# BLE112_Module.net
KiCad netlist of a schematic drawn in Altium Designer
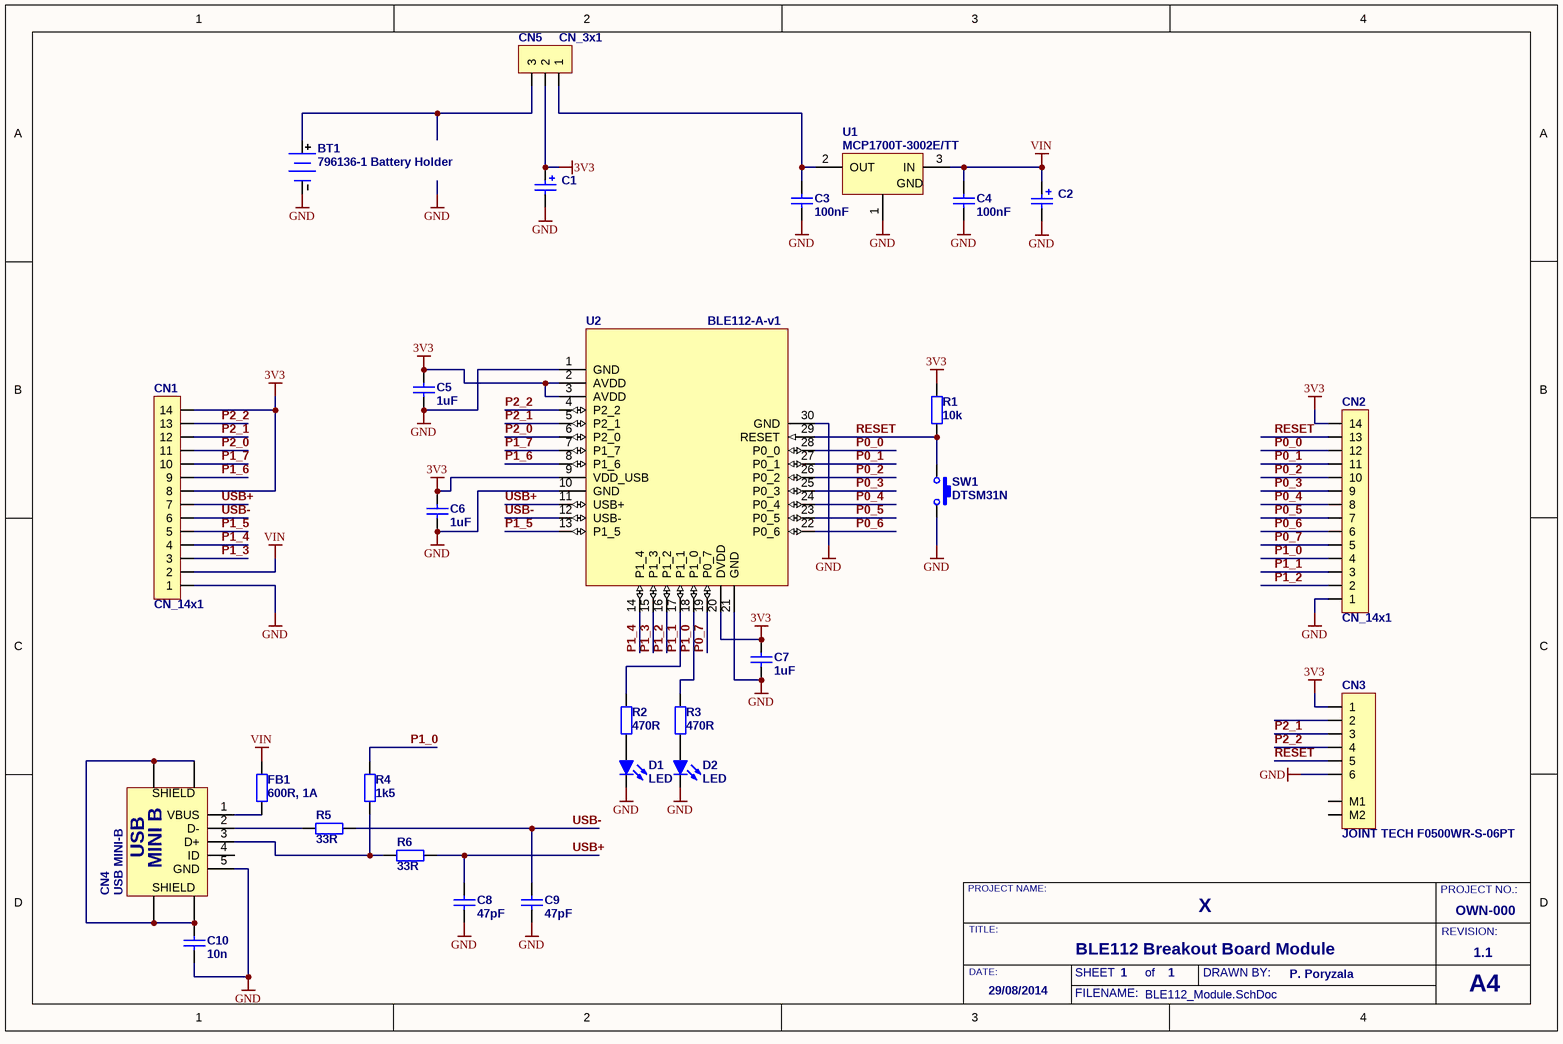
[diagram p0: BLE112_Module.SchDoc]

(export (version "E")
  (design (tool "Eeschema 10.0.6"))
  (components
    (comp (ref "BT1")
      (value "796136-1 Battery Holder")
      (footprint "796136-1")
      (description "Tyco Connectivity 796136-1 CR2032 Battery Holder")
      (fields (field (name "PUBLISHER") "Altium Limited"))
      (libsource (lib "baterries_and_accus") (part "796136-1"))
    )
    (comp (ref "C1")
      (value "~")
      (footprint "SMDB")
      (description "Polarized Tantalum Capacitor")
      (libsource (lib "capacitors") (part "Cap Pol Tant"))
    )
    (comp (ref "C2")
      (value "~")
      (footprint "SMDB")
      (description "Polarized Tantalum Capacitor")
      (libsource (lib "capacitors") (part "Cap Pol Tant"))
    )
    (comp (ref "C3")
      (value "100nF")
      (footprint "C0603")
      (description "Capacitor")
      (libsource (lib "capacitors") (part "Cap"))
    )
    (comp (ref "C4")
      (value "100nF")
      (footprint "C0603")
      (description "Capacitor")
      (libsource (lib "capacitors") (part "Cap"))
    )
    (comp (ref "C5")
      (value "1uF")
      (footprint "C0603")
      (description "Capacitor")
      (libsource (lib "capacitors") (part "Cap"))
    )
    (comp (ref "C6")
      (value "1uF")
      (footprint "C0603")
      (description "Capacitor")
      (libsource (lib "capacitors") (part "Cap"))
    )
    (comp (ref "C7")
      (value "1uF")
      (footprint "C0603")
      (description "Capacitor")
      (libsource (lib "capacitors") (part "Cap"))
    )
    (comp (ref "C8")
      (value "47pF")
      (footprint "C0603")
      (description "Capacitor")
      (libsource (lib "capacitors") (part "Cap"))
    )
    (comp (ref "C9")
      (value "47pF")
      (footprint "C0603")
      (description "Capacitor")
      (libsource (lib "capacitors") (part "Cap"))
    )
    (comp (ref "C10")
      (value "10n")
      (footprint "C0603")
      (description "Capacitor")
      (libsource (lib "capacitors") (part "Cap"))
    )
    (comp (ref "CN1") (value "CN_14x1") (footprint "GP_14x1") (libsource (lib "") (part "CN_14x1_1")))
    (comp (ref "CN2")
      (value "CN_14x1")
      (footprint "GP_14x1")
      (libsource (lib "goldpin_male") (part "CN_14x1"))
    )
    (comp (ref "CN3")
      (value "JOINT TECH F0500WR-S-06PT")
      (footprint "F0500WR-S-06PT")
      (description "0.50mm Pitch FFC/FPC Connector, SMT, Right Angle, ZIF, Top Contact Style Receptacle, 6 Circuits")
      (libsource (lib "ffc_fpc") (part "JOINT TECH F0500WR-S-06PT"))
    )
    (comp (ref "CN4")
      (value "USB MINI-B")
      (footprint "USB-MINI-B SMD")
      (description "USB Mini-B Receptacle")
      (libsource (lib "usb") (part "USB MINI-B"))
    )
    (comp (ref "CN5") (value "CN_3x1") (footprint "GP_3x1") (libsource (lib "goldpin_male") (part "CN_3x1")))
    (comp (ref "D1")
      (value "LED")
      (footprint "LED0603B")
      (description "Typical RED, GREEN, YELLOW, AMBER GaAs LED")
      (libsource (lib "leds") (part "LED"))
    )
    (comp (ref "D2")
      (value "LED")
      (footprint "LED0603R")
      (description "Typical RED, GREEN, YELLOW, AMBER GaAs LED")
      (libsource (lib "leds") (part "LED"))
    )
    (comp (ref "FB1")
      (value "600R, 1A")
      (footprint "FB0603")
      (description "Ferrite Bead; Imp.@ 100MHz:600R; Mounting: SMD; 1A; Case: 0603")
      (libsource (lib "emi_emc_ferrites") (part "LCBA-601"))
    )
    (comp (ref "R1")
      (value "10k")
      (footprint "R0603")
      (description "Resistor")
      (libsource (lib "resistors") (part "Res"))
    )
    (comp (ref "R2")
      (value "470R")
      (footprint "R0603")
      (description "Resistor")
      (libsource (lib "resistors") (part "Res"))
    )
    (comp (ref "R3")
      (value "470R")
      (footprint "R0603")
      (description "Resistor")
      (libsource (lib "resistors") (part "Res"))
    )
    (comp (ref "R4")
      (value "1k5")
      (footprint "R0603")
      (description "Resistor")
      (libsource (lib "") (part "Res_1"))
    )
    (comp (ref "R5")
      (value "33R")
      (footprint "R0603")
      (description "Resistor")
      (libsource (lib "") (part "Res_2"))
    )
    (comp (ref "R6")
      (value "33R")
      (footprint "R0603")
      (description "Resistor")
      (libsource (lib "") (part "Res_2"))
    )
    (comp (ref "SW1")
      (value "DTSM31N")
      (footprint "DTSM-3")
      (description "DIPTRONICS 6x3,5mm SMD Tactile SPST-NO Switch")
      (libsource (lib "microswitches") (part "DTSM31N"))
    )
    (comp (ref "U1")
      (value "MCP1700T-3002E/TT")
      (footprint "SOT-23")
      (description "250mA, Low Voltage, Low Quiescent Current (1.6uA) LDO Voltage Regulator")
      (fields (field (name "PUBLISHER") "Altium Limited"))
      (libsource (lib "voltage_regulators") (part "MCP1700T-3002E/TT"))
    )
    (comp (ref "U2")
      (value "BLE112-A-v1")
      (footprint "BLE112-x")
      (description "Bluetooth ®  low energy single mode module")
      (libsource (lib "rf_modules") (part "BLE112-A-v1"))
    )
  )
  (nets
    (net (code "1") (name "/P0_0") (class "Default")
      (node (ref "CN2") (pin "12") (pinfunction "12_12") (pintype "passive"))
      (node (ref "U2") (pin "28") (pinfunction "P0_0_28") (pintype "bidirectional"))
    )
    (net (code "2") (name "/P0_1") (class "Default")
      (node (ref "CN2") (pin "11") (pinfunction "11_11") (pintype "passive"))
      (node (ref "U2") (pin "27") (pinfunction "P0_1_27") (pintype "bidirectional"))
    )
    (net (code "3") (name "/P0_2") (class "Default")
      (node (ref "CN2") (pin "10") (pinfunction "10_10") (pintype "passive"))
      (node (ref "U2") (pin "26") (pinfunction "P0_2_26") (pintype "bidirectional"))
    )
    (net (code "4") (name "/P0_3") (class "Default")
      (node (ref "CN2") (pin "9") (pinfunction "9_9") (pintype "passive"))
      (node (ref "U2") (pin "25") (pinfunction "P0_3_25") (pintype "bidirectional"))
    )
    (net (code "5") (name "/P0_4") (class "Default")
      (node (ref "CN2") (pin "8") (pinfunction "8_8") (pintype "passive"))
      (node (ref "U2") (pin "24") (pinfunction "P0_4_24") (pintype "bidirectional"))
    )
    (net (code "6") (name "/P0_5") (class "Default")
      (node (ref "CN2") (pin "7") (pinfunction "7_7") (pintype "passive"))
      (node (ref "U2") (pin "23") (pinfunction "P0_5_23") (pintype "bidirectional"))
    )
    (net (code "7") (name "/P0_6") (class "Default")
      (node (ref "CN2") (pin "6") (pinfunction "6_6") (pintype "passive"))
      (node (ref "U2") (pin "22") (pinfunction "P0_6_22") (pintype "bidirectional"))
    )
    (net (code "8") (name "/P0_7") (class "Default")
      (node (ref "CN2") (pin "5") (pinfunction "5_5") (pintype "passive"))
      (node (ref "U2") (pin "19") (pinfunction "P0_7_19") (pintype "bidirectional"))
    )
    (net (code "9") (name "/P1_0") (class "Default")
      (node (ref "CN2") (pin "4") (pinfunction "4_4") (pintype "passive"))
      (node (ref "R3") (pin "2") (pinfunction "2_2") (pintype "passive"))
      (node (ref "R4") (pin "1") (pinfunction "1_1") (pintype "passive"))
      (node (ref "U2") (pin "18") (pinfunction "P1_0_18") (pintype "bidirectional"))
    )
    (net (code "10") (name "/P1_1") (class "Default")
      (node (ref "CN2") (pin "3") (pinfunction "3_3") (pintype "passive"))
      (node (ref "R2") (pin "2") (pinfunction "2_2") (pintype "passive"))
      (node (ref "U2") (pin "17") (pinfunction "P1_1_17") (pintype "bidirectional"))
    )
    (net (code "11") (name "/P1_2") (class "Default")
      (node (ref "CN2") (pin "2") (pinfunction "2_2") (pintype "passive"))
      (node (ref "U2") (pin "16") (pinfunction "P1_2_16") (pintype "bidirectional"))
    )
    (net (code "12") (name "/P1_3") (class "Default")
      (node (ref "CN1") (pin "3") (pinfunction "3_3") (pintype "passive"))
      (node (ref "U2") (pin "15") (pinfunction "P1_3_15") (pintype "bidirectional"))
    )
    (net (code "13") (name "/P1_4") (class "Default")
      (node (ref "CN1") (pin "4") (pinfunction "4_4") (pintype "passive"))
      (node (ref "U2") (pin "14") (pinfunction "P1_4_14") (pintype "bidirectional"))
    )
    (net (code "14") (name "/P1_5") (class "Default")
      (node (ref "CN1") (pin "5") (pinfunction "5_5") (pintype "passive"))
      (node (ref "U2") (pin "13") (pinfunction "P1_5_13") (pintype "bidirectional"))
    )
    (net (code "15") (name "/P1_6") (class "Default")
      (node (ref "CN1") (pin "9") (pinfunction "9_9") (pintype "passive"))
      (node (ref "U2") (pin "8") (pinfunction "P1_6_8") (pintype "bidirectional"))
    )
    (net (code "16") (name "/P1_7") (class "Default")
      (node (ref "CN1") (pin "10") (pinfunction "10_10") (pintype "passive"))
      (node (ref "U2") (pin "7") (pinfunction "P1_7_7") (pintype "bidirectional"))
    )
    (net (code "17") (name "/P2_0") (class "Default")
      (node (ref "CN1") (pin "11") (pinfunction "11_11") (pintype "passive"))
      (node (ref "U2") (pin "6") (pinfunction "P2_0_6") (pintype "bidirectional"))
    )
    (net (code "18") (name "/P2_1") (class "Default")
      (node (ref "CN1") (pin "12") (pinfunction "12_12") (pintype "passive"))
      (node (ref "CN3") (pin "3") (pinfunction "3_3") (pintype "passive"))
      (node (ref "U2") (pin "5") (pinfunction "P2_1_5") (pintype "bidirectional"))
    )
    (net (code "19") (name "/P2_2") (class "Default")
      (node (ref "CN1") (pin "13") (pinfunction "13_13") (pintype "passive"))
      (node (ref "CN3") (pin "4") (pinfunction "4_4") (pintype "passive"))
      (node (ref "U2") (pin "4") (pinfunction "P2_2_4") (pintype "bidirectional"))
    )
    (net (code "20") (name "/RESET") (class "Default")
      (node (ref "CN2") (pin "13") (pinfunction "13_13") (pintype "passive"))
      (node (ref "CN3") (pin "5") (pinfunction "5_5") (pintype "passive"))
      (node (ref "R1") (pin "1") (pinfunction "1_1") (pintype "passive"))
      (node (ref "SW1") (pin "1") (pinfunction "1_1") (pintype "passive"))
      (node (ref "U2") (pin "29") (pinfunction "RESET_29") (pintype "input"))
    )
    (net (code "21") (name "/USB+") (class "Default")
      (node (ref "C8") (pin "2") (pinfunction "2_2") (pintype "passive"))
      (node (ref "CN1") (pin "7") (pinfunction "7_7") (pintype "passive"))
      (node (ref "R6") (pin "1") (pinfunction "1_1") (pintype "passive"))
      (node (ref "U2") (pin "11") (pinfunction "USB+_11") (pintype "bidirectional"))
    )
    (net (code "22") (name "/USB-") (class "Default")
      (node (ref "C9") (pin "2") (pinfunction "2_2") (pintype "passive"))
      (node (ref "CN1") (pin "6") (pinfunction "6_6") (pintype "passive"))
      (node (ref "R5") (pin "1") (pinfunction "1_1") (pintype "passive"))
      (node (ref "U2") (pin "12") (pinfunction "USB-_12") (pintype "bidirectional"))
    )
    (net (code "23") (name "3V3") (class "Default")
      (node (ref "C1") (pin "1") (pinfunction "1_1") (pintype "passive"))
      (node (ref "C5") (pin "2") (pinfunction "2_2") (pintype "passive"))
      (node (ref "C6") (pin "2") (pinfunction "2_2") (pintype "passive"))
      (node (ref "C7") (pin "2") (pinfunction "2_2") (pintype "passive"))
      (node (ref "CN1") (pin "14") (pinfunction "14_14") (pintype "passive"))
      (node (ref "CN1") (pin "8") (pinfunction "8_8") (pintype "passive"))
      (node (ref "CN2") (pin "14") (pinfunction "14_14") (pintype "passive"))
      (node (ref "CN3") (pin "1") (pinfunction "1_1") (pintype "passive"))
      (node (ref "CN5") (pin "2") (pinfunction "2_2") (pintype "passive"))
      (node (ref "R1") (pin "2") (pinfunction "2_2") (pintype "passive"))
      (node (ref "U2") (pin "2") (pinfunction "AVDD_2") (pintype "power_in"))
      (node (ref "U2") (pin "20") (pinfunction "DVDD_20") (pintype "power_in"))
      (node (ref "U2") (pin "3") (pinfunction "AVDD_3") (pintype "power_in"))
      (node (ref "U2") (pin "9") (pinfunction "VDD_USB_9") (pintype "power_in"))
    )
    (net (code "24") (name "GND") (class "Default")
      (node (ref "BT1") (pin "2") (pinfunction "-_2") (pintype "passive"))
      (node (ref "C1") (pin "2") (pinfunction "2_2") (pintype "passive"))
      (node (ref "C10") (pin "1") (pinfunction "1_1") (pintype "passive"))
      (node (ref "C2") (pin "2") (pinfunction "2_2") (pintype "passive"))
      (node (ref "C3") (pin "1") (pinfunction "1_1") (pintype "passive"))
      (node (ref "C4") (pin "1") (pinfunction "1_1") (pintype "passive"))
      (node (ref "C5") (pin "1") (pinfunction "1_1") (pintype "passive"))
      (node (ref "C6") (pin "1") (pinfunction "1_1") (pintype "passive"))
      (node (ref "C7") (pin "1") (pinfunction "1_1") (pintype "passive"))
      (node (ref "C8") (pin "1") (pinfunction "1_1") (pintype "passive"))
      (node (ref "C9") (pin "1") (pinfunction "1_1") (pintype "passive"))
      (node (ref "CN1") (pin "1") (pinfunction "1_1") (pintype "passive"))
      (node (ref "CN2") (pin "1") (pinfunction "1_1") (pintype "passive"))
      (node (ref "CN3") (pin "6") (pinfunction "6_6") (pintype "passive"))
      (node (ref "CN4") (pin "5") (pinfunction "GND_5") (pintype "passive"))
      (node (ref "D1") (pin "2") (pinfunction "K_2") (pintype "passive"))
      (node (ref "D2") (pin "2") (pinfunction "K_2") (pintype "passive"))
      (node (ref "SW1") (pin "2") (pinfunction "2_2") (pintype "passive"))
      (node (ref "U1") (pin "1") (pinfunction "GND_1") (pintype "power_in"))
      (node (ref "U2") (pin "1") (pinfunction "GND_1") (pintype "power_in"))
      (node (ref "U2") (pin "10") (pinfunction "GND_10") (pintype "power_in"))
      (node (ref "U2") (pin "21") (pinfunction "GND_21") (pintype "power_in"))
      (node (ref "U2") (pin "30") (pinfunction "GND_30") (pintype "power_in"))
    )
    (net (code "25") (name "Net-(BT1-+)") (class "Default")
      (node (ref "BT1") (pin "1") (pinfunction "+_1") (pintype "passive"))
      (node (ref "CN5") (pin "3") (pinfunction "3_3") (pintype "passive"))
    )
    (net (code "26") (name "Net-(C10-Pad2)") (class "Default")
      (node (ref "C10") (pin "2") (pinfunction "2_2") (pintype "passive"))
      (node (ref "CN4") (pin "6") (pinfunction "SHIELD_6") (pintype "passive"))
      (node (ref "CN4") (pin "7") (pinfunction "SHIELD_7") (pintype "passive"))
      (node (ref "CN4") (pin "8") (pinfunction "SHIELD_8") (pintype "passive"))
      (node (ref "CN4") (pin "9") (pinfunction "SHIELD_9") (pintype "passive"))
    )
    (net (code "27") (name "Net-(CN4-D+)") (class "Default")
      (node (ref "CN4") (pin "3") (pinfunction "D+_3") (pintype "passive"))
      (node (ref "R4") (pin "2") (pinfunction "2_2") (pintype "passive"))
      (node (ref "R6") (pin "2") (pinfunction "2_2") (pintype "passive"))
    )
    (net (code "28") (name "Net-(CN4-D-)") (class "Default")
      (node (ref "CN4") (pin "2") (pinfunction "D-_2") (pintype "passive"))
      (node (ref "R5") (pin "2") (pinfunction "2_2") (pintype "passive"))
    )
    (net (code "29") (name "Net-(CN4-VBUS)") (class "Default")
      (node (ref "CN4") (pin "1") (pinfunction "VBUS_1") (pintype "passive"))
      (node (ref "FB1") (pin "1") (pinfunction "1_1") (pintype "passive"))
    )
    (net (code "30") (name "Net-(D1-A)") (class "Default")
      (node (ref "D1") (pin "1") (pinfunction "A_1") (pintype "passive"))
      (node (ref "R2") (pin "1") (pinfunction "1_1") (pintype "passive"))
    )
    (net (code "31") (name "Net-(D2-A)") (class "Default")
      (node (ref "D2") (pin "1") (pinfunction "A_1") (pintype "passive"))
      (node (ref "R3") (pin "1") (pinfunction "1_1") (pintype "passive"))
    )
    (net (code "32") (name "Net-(U1-OUT)") (class "Default")
      (node (ref "C3") (pin "2") (pinfunction "2_2") (pintype "passive"))
      (node (ref "CN5") (pin "1") (pinfunction "1_1") (pintype "passive"))
      (node (ref "U1") (pin "2") (pinfunction "OUT_2") (pintype "power_in"))
    )
    (net (code "33") (name "VIN") (class "Default")
      (node (ref "C2") (pin "1") (pinfunction "1_1") (pintype "passive"))
      (node (ref "C4") (pin "2") (pinfunction "2_2") (pintype "passive"))
      (node (ref "CN1") (pin "2") (pinfunction "2_2") (pintype "passive"))
      (node (ref "FB1") (pin "2") (pinfunction "2_2") (pintype "passive"))
      (node (ref "U1") (pin "3") (pinfunction "IN_3") (pintype "power_in"))
    )
    (net (code "34") (name "unconnected-(CN3-M1-Pad9)") (class "Default")
      (node (ref "CN3") (pin "9") (pinfunction "M1_9") (pintype "passive"))
    )
    (net (code "35") (name "unconnected-(CN3-M2-Pad10)") (class "Default")
      (node (ref "CN3") (pin "10") (pinfunction "M2_10") (pintype "passive"))
    )
    (net (code "36") (name "unconnected-(CN3-Pad2)") (class "Default")
      (node (ref "CN3") (pin "2") (pinfunction "2_2") (pintype "passive"))
    )
    (net (code "37") (name "unconnected-(CN4-ID-Pad4)") (class "Default")
      (node (ref "CN4") (pin "4") (pinfunction "ID_4") (pintype "passive"))
    )
  )
)
